# MAX96751_PINOUT.net
KiCad netlist of a schematic drawn in Altium Designer
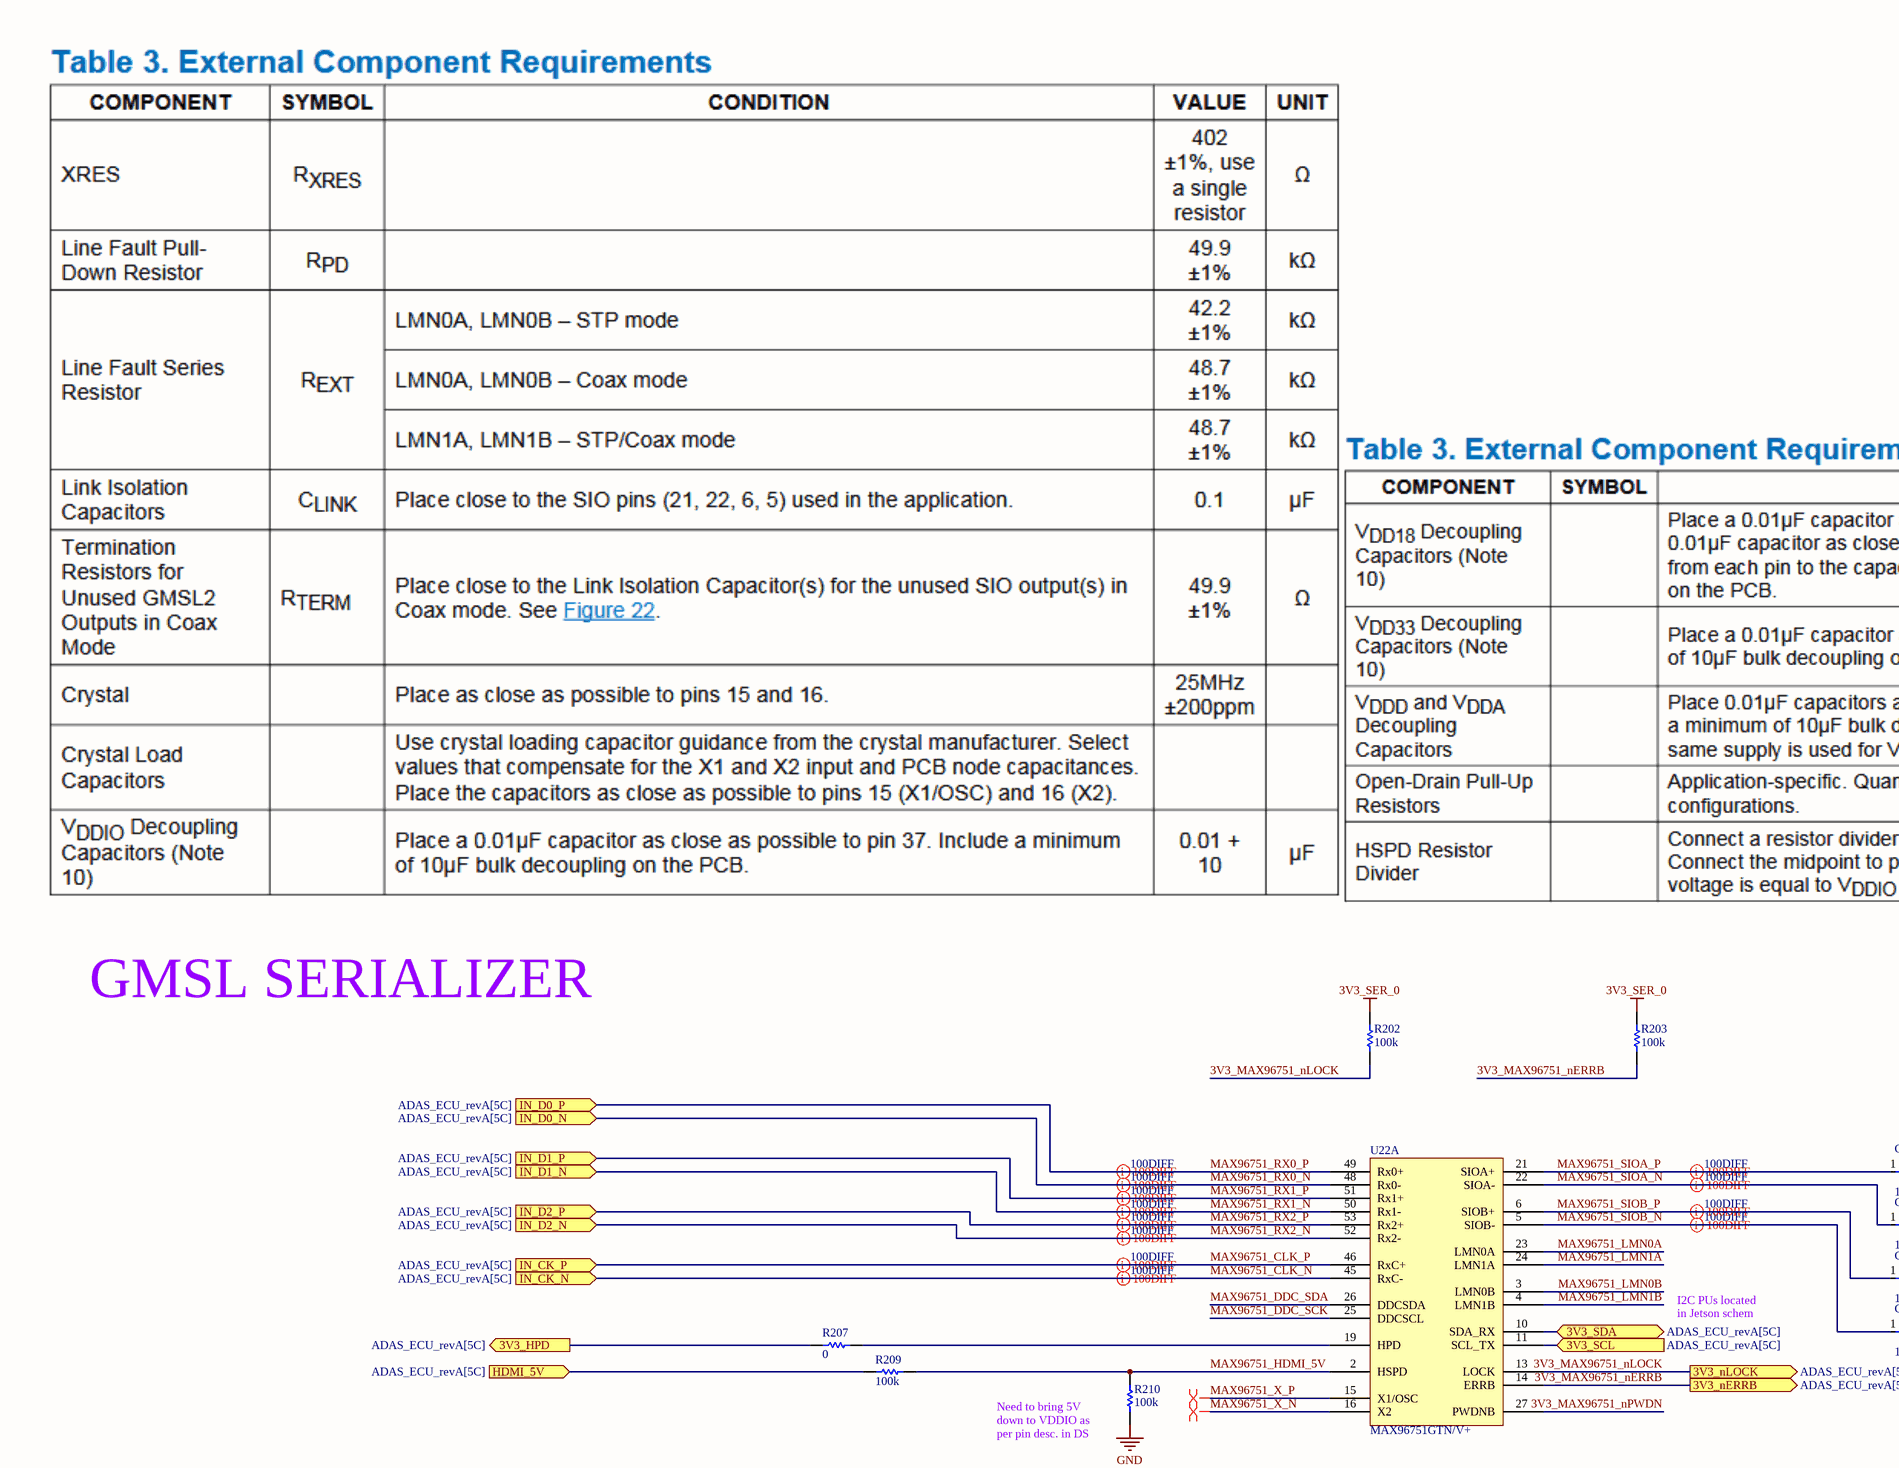
[diagram p0: MAX96751_PINOUT.SchDoc, top left]
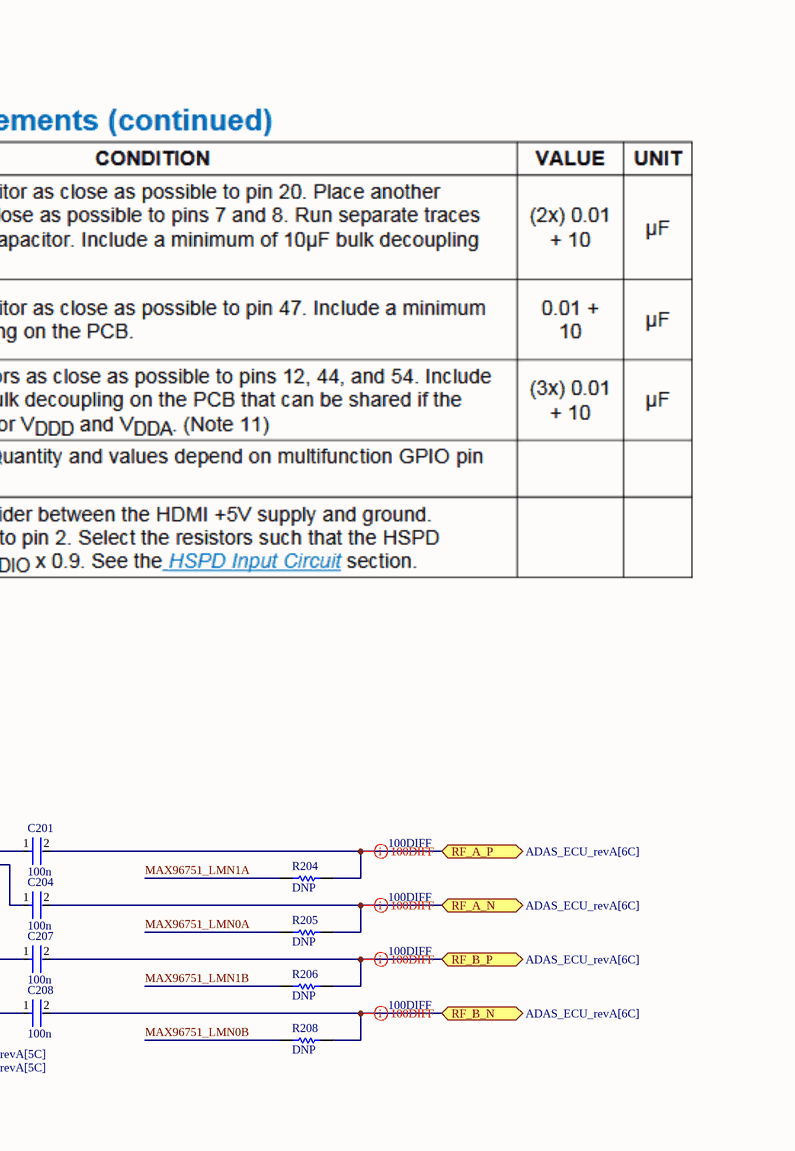
[diagram p1: MAX96751_PINOUT.SchDoc, top right]
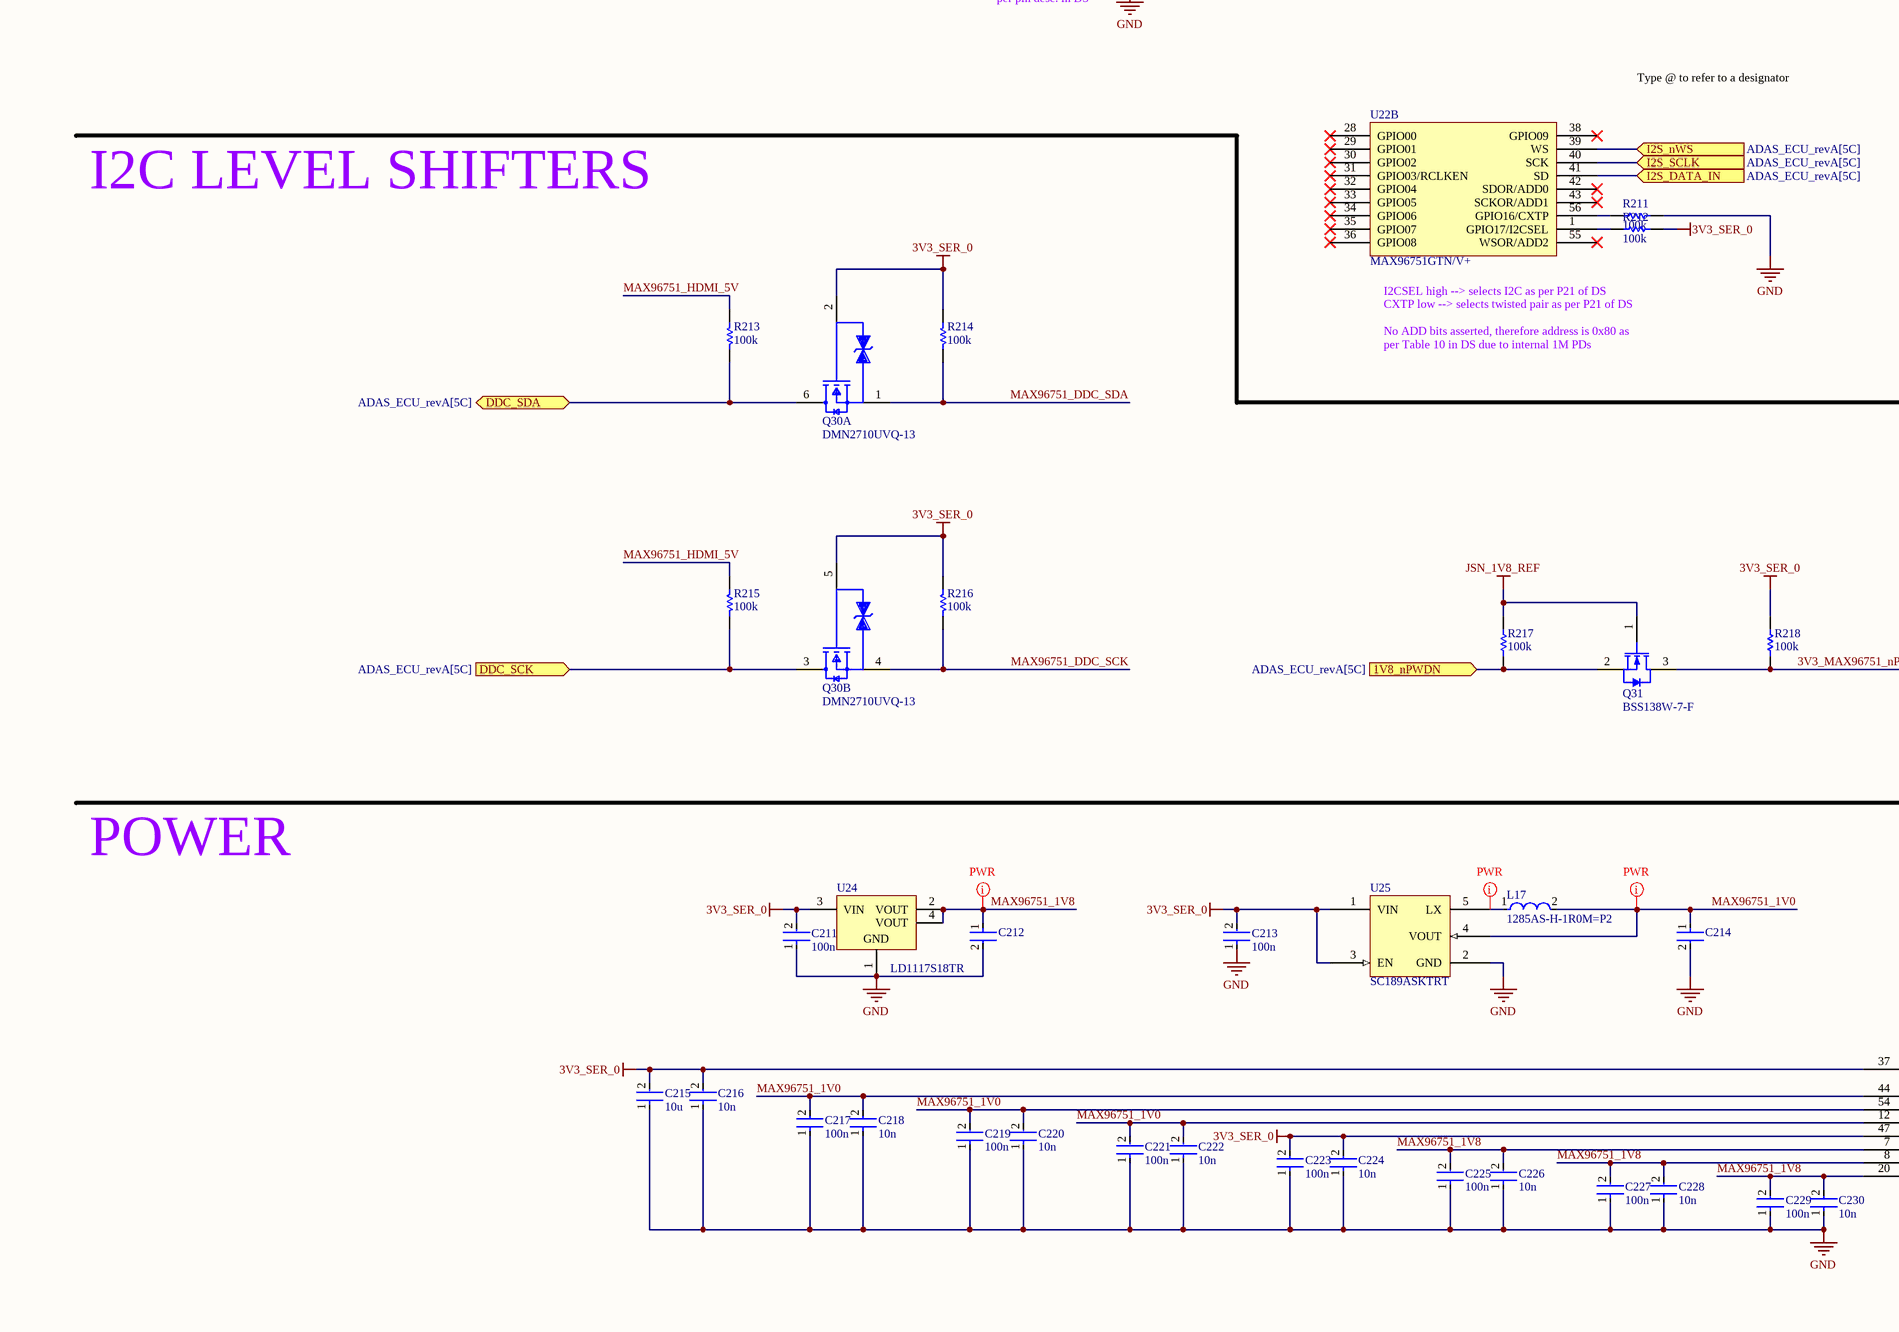
[diagram p2: MAX96751_PINOUT.SchDoc, bottom left]
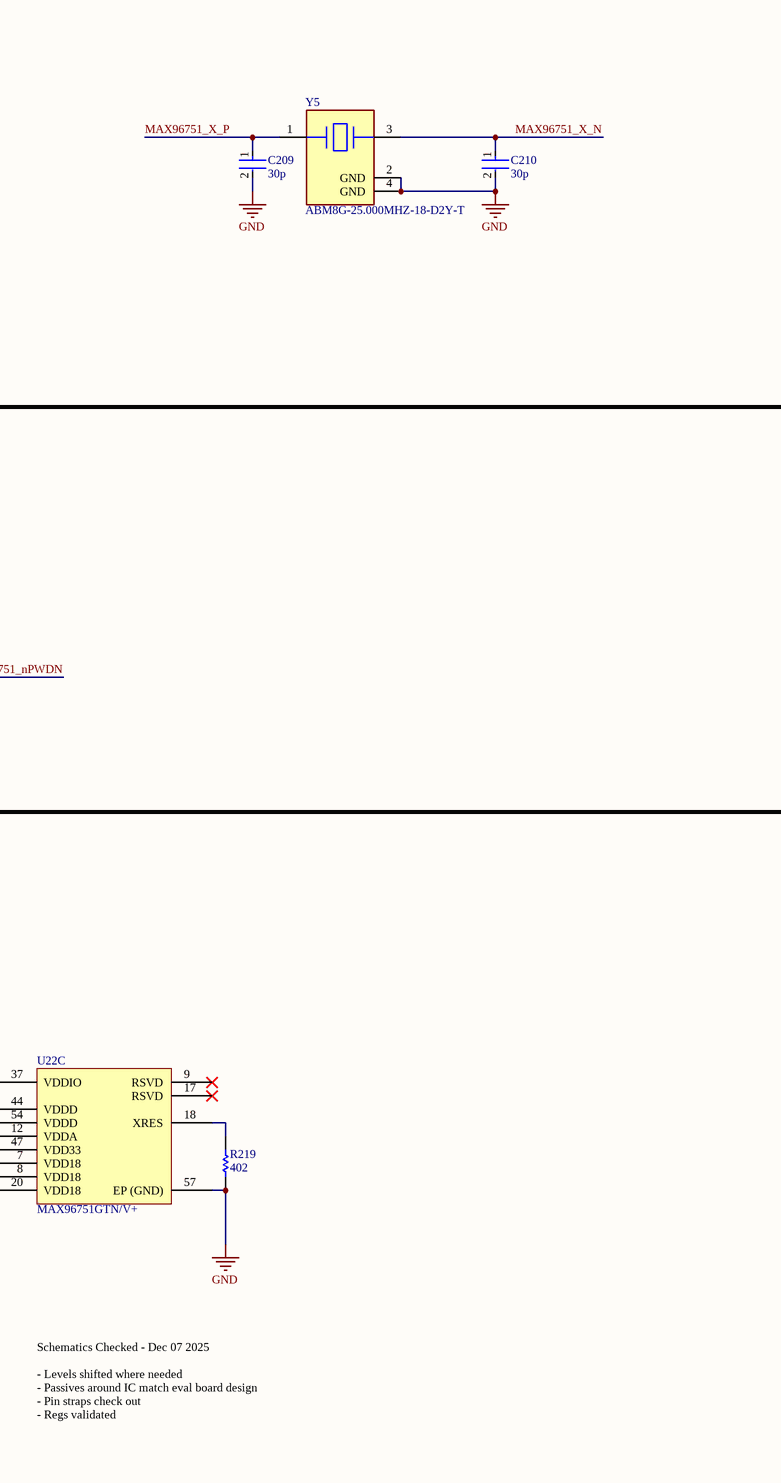
[diagram p3: MAX96751_PINOUT.SchDoc, bottom right]

(export (version "E")
  (design (tool "Eeschema 10.0.6"))
  (components
    (comp (ref "C201")
      (value "100n")
      (footprint "FP-0402-L_1_0_0_05-W_0_5-IPC_A")
      (description "LARGE PADS, 0402 CAP, CHANGE COMMENT TO MATCH REAL P/N")
      (libsource (lib "Space Concordia") (part "b4654b650e69147ec39a6b967a45e02"))
    )
    (comp (ref "C204")
      (value "100n")
      (footprint "FP-0402-L_1_0_0_05-W_0_5-IPC_A")
      (description "LARGE PADS, 0402 CAP, CHANGE COMMENT TO MATCH REAL P/N")
      (libsource (lib "Space Concordia") (part "b4654b650e69147ec39a6b967a45e02"))
    )
    (comp (ref "C207")
      (value "100n")
      (footprint "FP-0402-L_1_0_0_05-W_0_5-IPC_A")
      (description "LARGE PADS, 0402 CAP, CHANGE COMMENT TO MATCH REAL P/N")
      (libsource (lib "Space Concordia") (part "b4654b650e69147ec39a6b967a45e02"))
    )
    (comp (ref "C208")
      (value "100n")
      (footprint "FP-0402-L_1_0_0_05-W_0_5-IPC_A")
      (description "LARGE PADS, 0402 CAP, CHANGE COMMENT TO MATCH REAL P/N")
      (libsource (lib "Space Concordia") (part "b4654b650e69147ec39a6b967a45e02"))
    )
    (comp (ref "C209")
      (value "30p")
      (footprint "FP-0402-L_1_0_0_05-W_0_5-IPC_A")
      (description "LARGE PADS, 0402 CAP, CHANGE COMMENT TO MATCH REAL P/N")
      (libsource (lib "Space Concordia") (part "b4654b650e69147ec39a6b967a45e02"))
    )
    (comp (ref "C210")
      (value "30p")
      (footprint "FP-0402-L_1_0_0_05-W_0_5-IPC_A")
      (description "LARGE PADS, 0402 CAP, CHANGE COMMENT TO MATCH REAL P/N")
      (libsource (lib "Space Concordia") (part "b4654b650e69147ec39a6b967a45e02"))
    )
    (comp (ref "C211")
      (value "100n")
      (footprint "FP-0402-L_1_0_0_05-W_0_5-IPC_A")
      (description "LARGE PADS, 0402 CAP, CHANGE COMMENT TO MATCH REAL P/N")
      (libsource (lib "Space Concordia") (part "b4654b650e69147ec39a6b967a45e02"))
    )
    (comp (ref "C212")
      (value "GRM188R60J106ME47D")
      (footprint "FP-GRM188-0_1-e0_2_0_55-IPC_A")
      (description "Chip Multilayer Ceramic Capacitors for General Purpose, 0603, 10uF, X5R, 15%, 20%, 6.3V")
      (fields (field (name "VOLTAGE") "6.3V") (field (name "TOLERANCE") "20%"))
      (libsource (lib "Altium Content Vault") (part "02cd4be3c70576c341d710602a673aa"))
    )
    (comp (ref "C213")
      (value "100n")
      (footprint "FP-0402-L_1_0_0_05-W_0_5-IPC_A")
      (description "LARGE PADS, 0402 CAP, CHANGE COMMENT TO MATCH REAL P/N")
      (libsource (lib "Space Concordia") (part "b4654b650e69147ec39a6b967a45e02"))
    )
    (comp (ref "C214")
      (value "GRM21BR61E226ME44L")
      (footprint "FP-GRM21B-0_2-e0_2_0_7-IPC_B")
      (description "Chip Multilayer Ceramic Capacitors for General Purpose, 0805, 22uF, X5R, 15%, 20%, 25V")
      (fields (field (name "TOLERANCE") "20%") (field (name "VOLTAGE") "25V"))
      (libsource (lib "Altium Content Vault") (part "b4654b650e69147ec39a6b967a45e02"))
    )
    (comp (ref "C215")
      (value "10u")
      (footprint "FP-0402-L_1_0_0_05-W_0_5-IPC_A")
      (description "LARGE PADS, 0402 CAP, CHANGE COMMENT TO MATCH REAL P/N")
      (libsource (lib "Space Concordia") (part "b4654b650e69147ec39a6b967a45e02"))
    )
    (comp (ref "C216")
      (value "10n")
      (footprint "FP-0402-L_1_0_0_05-W_0_5-IPC_A")
      (description "LARGE PADS, 0402 CAP, CHANGE COMMENT TO MATCH REAL P/N")
      (libsource (lib "Space Concordia") (part "b4654b650e69147ec39a6b967a45e02"))
    )
    (comp (ref "C217")
      (value "100n")
      (footprint "FP-0402-L_1_0_0_05-W_0_5-IPC_A")
      (description "LARGE PADS, 0402 CAP, CHANGE COMMENT TO MATCH REAL P/N")
      (libsource (lib "Space Concordia") (part "b4654b650e69147ec39a6b967a45e02"))
    )
    (comp (ref "C218")
      (value "10n")
      (footprint "FP-0402-L_1_0_0_05-W_0_5-IPC_A")
      (description "LARGE PADS, 0402 CAP, CHANGE COMMENT TO MATCH REAL P/N")
      (libsource (lib "Space Concordia") (part "b4654b650e69147ec39a6b967a45e02"))
    )
    (comp (ref "C219")
      (value "100n")
      (footprint "FP-0402-L_1_0_0_05-W_0_5-IPC_A")
      (description "LARGE PADS, 0402 CAP, CHANGE COMMENT TO MATCH REAL P/N")
      (libsource (lib "Space Concordia") (part "b4654b650e69147ec39a6b967a45e02"))
    )
    (comp (ref "C220")
      (value "10n")
      (footprint "FP-0402-L_1_0_0_05-W_0_5-IPC_A")
      (description "LARGE PADS, 0402 CAP, CHANGE COMMENT TO MATCH REAL P/N")
      (libsource (lib "Space Concordia") (part "b4654b650e69147ec39a6b967a45e02"))
    )
    (comp (ref "C221")
      (value "100n")
      (footprint "FP-0402-L_1_0_0_05-W_0_5-IPC_A")
      (description "LARGE PADS, 0402 CAP, CHANGE COMMENT TO MATCH REAL P/N")
      (libsource (lib "Space Concordia") (part "b4654b650e69147ec39a6b967a45e02"))
    )
    (comp (ref "C222")
      (value "10n")
      (footprint "FP-0402-L_1_0_0_05-W_0_5-IPC_A")
      (description "LARGE PADS, 0402 CAP, CHANGE COMMENT TO MATCH REAL P/N")
      (libsource (lib "Space Concordia") (part "b4654b650e69147ec39a6b967a45e02"))
    )
    (comp (ref "C223")
      (value "100n")
      (footprint "FP-0402-L_1_0_0_05-W_0_5-IPC_A")
      (description "LARGE PADS, 0402 CAP, CHANGE COMMENT TO MATCH REAL P/N")
      (libsource (lib "Space Concordia") (part "b4654b650e69147ec39a6b967a45e02"))
    )
    (comp (ref "C224")
      (value "10n")
      (footprint "FP-0402-L_1_0_0_05-W_0_5-IPC_A")
      (description "LARGE PADS, 0402 CAP, CHANGE COMMENT TO MATCH REAL P/N")
      (libsource (lib "Space Concordia") (part "b4654b650e69147ec39a6b967a45e02"))
    )
    (comp (ref "C225")
      (value "100n")
      (footprint "FP-0402-L_1_0_0_05-W_0_5-IPC_A")
      (description "LARGE PADS, 0402 CAP, CHANGE COMMENT TO MATCH REAL P/N")
      (libsource (lib "Space Concordia") (part "b4654b650e69147ec39a6b967a45e02"))
    )
    (comp (ref "C226")
      (value "10n")
      (footprint "FP-0402-L_1_0_0_05-W_0_5-IPC_A")
      (description "LARGE PADS, 0402 CAP, CHANGE COMMENT TO MATCH REAL P/N")
      (libsource (lib "Space Concordia") (part "b4654b650e69147ec39a6b967a45e02"))
    )
    (comp (ref "C227")
      (value "100n")
      (footprint "FP-0402-L_1_0_0_05-W_0_5-IPC_A")
      (description "LARGE PADS, 0402 CAP, CHANGE COMMENT TO MATCH REAL P/N")
      (libsource (lib "Space Concordia") (part "b4654b650e69147ec39a6b967a45e02"))
    )
    (comp (ref "C228")
      (value "10n")
      (footprint "FP-0402-L_1_0_0_05-W_0_5-IPC_A")
      (description "LARGE PADS, 0402 CAP, CHANGE COMMENT TO MATCH REAL P/N")
      (libsource (lib "Space Concordia") (part "b4654b650e69147ec39a6b967a45e02"))
    )
    (comp (ref "C229")
      (value "100n")
      (footprint "FP-0402-L_1_0_0_05-W_0_5-IPC_A")
      (description "LARGE PADS, 0402 CAP, CHANGE COMMENT TO MATCH REAL P/N")
      (libsource (lib "Space Concordia") (part "b4654b650e69147ec39a6b967a45e02"))
    )
    (comp (ref "C230")
      (value "10n")
      (footprint "FP-0402-L_1_0_0_05-W_0_5-IPC_A")
      (description "LARGE PADS, 0402 CAP, CHANGE COMMENT TO MATCH REAL P/N")
      (libsource (lib "Space Concordia") (part "b4654b650e69147ec39a6b967a45e02"))
    )
    (comp (ref "L17")
      (value "1285AS-H-1R0M=P2")
      (footprint "FP-DFE201610C-MFG")
      (description "FIXED IND 1UH 2.2A 96 MOHM SMD")
      (fields (field (name "TOLERANCE") "20%"))
      (libsource (lib "Altium Content Vault") (part "725321dda6339637d4d059423bc1c3c"))
    )
    (comp (ref "Q30")
      (value "DMN2710UVQ-13")
      (footprint "SOTFL50P162X60-6N")
      (description "MOSFET Array, Dual N Channel, 20 V, 920 mA, 450 Milliohms, SOT-563, 6 Pins")
      (libsource (lib "Space Concordia") (part "DMN2710UVQ-13"))
    )
    (comp (ref "Q31")
      (value "BSS138W-7-F")
      (footprint "DIOD-SOT323-3_V")
      (fields (field (name "MANUFACTURER") "DiodesIncorporated"))
      (libsource (lib "Altium Content Vault") (part "NEMOS-GSD-3"))
    )
    (comp (ref "R202")
      (value "100k")
      (footprint "R0603B")
      (description "Resistor")
      (libsource (lib "Space Concordia") (part "Resistor"))
    )
    (comp (ref "R203")
      (value "100k")
      (footprint "R0603B")
      (description "Resistor")
      (libsource (lib "Space Concordia") (part "Resistor"))
    )
    (comp (ref "R204")
      (value "DNP")
      (footprint "R0603B")
      (description "Resistor")
      (libsource (lib "Space Concordia") (part "Resistor"))
    )
    (comp (ref "R205")
      (value "DNP")
      (footprint "R0603B")
      (description "Resistor")
      (libsource (lib "Space Concordia") (part "Resistor"))
    )
    (comp (ref "R206")
      (value "DNP")
      (footprint "R0603B")
      (description "Resistor")
      (libsource (lib "Space Concordia") (part "Resistor"))
    )
    (comp (ref "R207")
      (value "0")
      (footprint "R0603B")
      (description "Resistor")
      (libsource (lib "Space Concordia") (part "Resistor"))
    )
    (comp (ref "R208")
      (value "DNP")
      (footprint "R0603B")
      (description "Resistor")
      (libsource (lib "Space Concordia") (part "Resistor"))
    )
    (comp (ref "R209")
      (value "100k")
      (footprint "R0603B")
      (description "Resistor")
      (libsource (lib "Space Concordia") (part "Resistor"))
    )
    (comp (ref "R210")
      (value "100k")
      (footprint "R0603B")
      (description "Resistor")
      (libsource (lib "Space Concordia") (part "Resistor"))
    )
    (comp (ref "R211")
      (value "100k")
      (footprint "R0603B")
      (description "Resistor")
      (libsource (lib "Space Concordia") (part "Resistor"))
    )
    (comp (ref "R212")
      (value "100k")
      (footprint "R0603B")
      (description "Resistor")
      (libsource (lib "Space Concordia") (part "Resistor"))
    )
    (comp (ref "R213")
      (value "100k")
      (footprint "R0603B")
      (description "Resistor")
      (libsource (lib "Space Concordia") (part "Resistor"))
    )
    (comp (ref "R214")
      (value "100k")
      (footprint "R0603B")
      (description "Resistor")
      (libsource (lib "Space Concordia") (part "Resistor"))
    )
    (comp (ref "R215")
      (value "100k")
      (footprint "R0603B")
      (description "Resistor")
      (libsource (lib "Space Concordia") (part "Resistor"))
    )
    (comp (ref "R216")
      (value "100k")
      (footprint "R0603B")
      (description "Resistor")
      (libsource (lib "Space Concordia") (part "Resistor"))
    )
    (comp (ref "R217")
      (value "100k")
      (footprint "R0603B")
      (description "Resistor")
      (libsource (lib "Space Concordia") (part "Resistor"))
    )
    (comp (ref "R218")
      (value "100k")
      (footprint "R0603B")
      (description "Resistor")
      (libsource (lib "Space Concordia") (part "Resistor"))
    )
    (comp (ref "R219")
      (value "402")
      (footprint "R0603B")
      (description "Resistor")
      (libsource (lib "Space Concordia") (part "Resistor"))
    )
    (comp (ref "U22")
      (value "MAX96751GTN/V+")
      (footprint "QFN50P800X800X80_HS-57N")
      (description "GMSL2 Serializer with HDMI 2.0 Input")
      (libsource (lib "Space Concordia") (part "MAX96751GTN_V+"))
    )
    (comp (ref "U24")
      (value "LD1117S18TR")
      (footprint "SOT-223_M")
      (description "Fixed Low Drop Positive Voltage Regulator, 1.8V, 4-Pin SOT-223, Tape and Reel")
      (libsource (lib "Altium Content Vault") (part "PM-REG-LD1117-SOT4"))
    )
    (comp (ref "U25")
      (value "SC189ASKTRT")
      (footprint "SOT95P275X145-5N")
      (description "Switching Regulator, Voltage-mode, 1.5A, 3000kHz Switching Freq-Max, PDSO5")
      (libsource (lib "Space Concordia") (part "SC189ASKTRT"))
    )
    (comp (ref "Y5")
      (value "ABM8G-25.000MHZ-18-D2Y-T")
      (footprint "FP-ABM8G-MFG")
      (description "Crystal 25MHz ±20ppm (Tol) ±30ppm (Stability) 18pF FUND 60Ω 4-Pin SMD T/R")
      (fields (field (name "TOLERANCE") "20ppm"))
      (libsource (lib "Altium Content Vault") (part "48e526d86b7f2615d98721063c72f49"))
    )
  )
  (nets
    (net (code "1") (name "/1V8_nPWDN") (class "Default")
      (node (ref "Q31") (pin "2") (pinfunction "S_2") (pintype "passive"))
      (node (ref "R217") (pin "1") (pinfunction "1_1") (pintype "passive"))
    )
    (net (code "2") (name "/3V3_HPD") (class "Default")
      (node (ref "R207") (pin "2") (pinfunction "2_2") (pintype "passive"))
    )
    (net (code "3") (name "/3V3_MAX96751_nERRB") (class "Default")
      (node (ref "R203") (pin "1") (pinfunction "1_1") (pintype "passive"))
      (node (ref "U22") (pin "14") (pinfunction "ERRB_14") (pintype "passive"))
    )
    (net (code "4") (name "/3V3_MAX96751_nLOCK") (class "Default")
      (node (ref "R202") (pin "1") (pinfunction "1_1") (pintype "passive"))
      (node (ref "U22") (pin "13") (pinfunction "LOCK_13") (pintype "passive"))
    )
    (net (code "5") (name "/3V3_MAX96751_nPWDN") (class "Default")
      (node (ref "Q31") (pin "3") (pinfunction "D_3") (pintype "passive"))
      (node (ref "R218") (pin "1") (pinfunction "1_1") (pintype "passive"))
      (node (ref "U22") (pin "27") (pinfunction "PWDNB_27") (pintype "passive"))
    )
    (net (code "6") (name "/3V3_SCL") (class "Default")
      (node (ref "U22") (pin "11") (pinfunction "SCL_TX_11") (pintype "passive"))
    )
    (net (code "7") (name "/3V3_SDA") (class "Default")
      (node (ref "U22") (pin "10") (pinfunction "SDA_RX_10") (pintype "passive"))
    )
    (net (code "8") (name "/DDC_SCK") (class "Default")
      (node (ref "Q30") (pin "3") (pinfunction "Drain2_3") (pintype "passive"))
      (node (ref "R215") (pin "1") (pinfunction "1_1") (pintype "passive"))
    )
    (net (code "9") (name "/DDC_SDA") (class "Default")
      (node (ref "Q30") (pin "6") (pinfunction "Drain1_6") (pintype "passive"))
      (node (ref "R213") (pin "1") (pinfunction "1_1") (pintype "passive"))
    )
    (net (code "10") (name "/HDMI_5V") (class "Default")
      (node (ref "R209") (pin "2") (pinfunction "2_2") (pintype "passive"))
    )
    (net (code "11") (name "/I2S_DATA_IN") (class "Default")
      (node (ref "U22") (pin "41") (pinfunction "SD_41") (pintype "passive"))
    )
    (net (code "12") (name "/I2S_SCLK") (class "Default")
      (node (ref "U22") (pin "40") (pinfunction "SCK_40") (pintype "passive"))
    )
    (net (code "13") (name "/I2S_nWS") (class "Default")
      (node (ref "U22") (pin "39") (pinfunction "WS_39") (pintype "passive"))
    )
    (net (code "14") (name "/MAX96751_1V0") (class "Default")
      (node (ref "C214") (pin "1") (pinfunction "1_1") (pintype "passive"))
      (node (ref "C217") (pin "2") (pinfunction "2_2") (pintype "passive"))
      (node (ref "C218") (pin "2") (pinfunction "2_2") (pintype "passive"))
      (node (ref "C219") (pin "2") (pinfunction "2_2") (pintype "passive"))
      (node (ref "C220") (pin "2") (pinfunction "2_2") (pintype "passive"))
      (node (ref "C221") (pin "2") (pinfunction "2_2") (pintype "passive"))
      (node (ref "C222") (pin "2") (pinfunction "2_2") (pintype "passive"))
      (node (ref "L17") (pin "2") (pinfunction "2_2") (pintype "passive"))
      (node (ref "U22") (pin "12") (pinfunction "VDDA_12") (pintype "passive"))
      (node (ref "U22") (pin "44") (pinfunction "VDDD_44") (pintype "passive"))
      (node (ref "U22") (pin "54") (pinfunction "VDDD_54") (pintype "passive"))
      (node (ref "U25") (pin "4") (pinfunction "VOUT_4") (pintype "input"))
    )
    (net (code "15") (name "/MAX96751_1V8") (class "Default")
      (node (ref "C212") (pin "1") (pinfunction "1_1") (pintype "passive"))
      (node (ref "C225") (pin "2") (pinfunction "2_2") (pintype "passive"))
      (node (ref "C226") (pin "2") (pinfunction "2_2") (pintype "passive"))
      (node (ref "C227") (pin "2") (pinfunction "2_2") (pintype "passive"))
      (node (ref "C228") (pin "2") (pinfunction "2_2") (pintype "passive"))
      (node (ref "C229") (pin "2") (pinfunction "2_2") (pintype "passive"))
      (node (ref "C230") (pin "2") (pinfunction "2_2") (pintype "passive"))
      (node (ref "U22") (pin "20") (pinfunction "VDD18_20") (pintype "passive"))
      (node (ref "U22") (pin "7") (pinfunction "VDD18_7") (pintype "passive"))
      (node (ref "U22") (pin "8") (pinfunction "VDD18_8") (pintype "passive"))
      (node (ref "U24") (pin "2") (pinfunction "VOUT_2") (pintype "power_in"))
      (node (ref "U24") (pin "4") (pinfunction "VOUT_4") (pintype "power_in"))
    )
    (net (code "16") (name "/MAX96751_CLK_N") (class "Default")
      (node (ref "U22") (pin "45") (pinfunction "RxC-_45") (pintype "passive"))
    )
    (net (code "17") (name "/MAX96751_CLK_P") (class "Default")
      (node (ref "U22") (pin "46") (pinfunction "RxC+_46") (pintype "passive"))
    )
    (net (code "18") (name "/MAX96751_DDC_SCK") (class "Default")
      (node (ref "Q30") (pin "4") (pinfunction "Source2_4") (pintype "passive"))
      (node (ref "R216") (pin "1") (pinfunction "1_1") (pintype "passive"))
      (node (ref "U22") (pin "25") (pinfunction "DDCSCL_25") (pintype "passive"))
    )
    (net (code "19") (name "/MAX96751_DDC_SDA") (class "Default")
      (node (ref "Q30") (pin "1") (pinfunction "Source1_1") (pintype "passive"))
      (node (ref "R214") (pin "1") (pinfunction "1_1") (pintype "passive"))
      (node (ref "U22") (pin "26") (pinfunction "DDCSDA_26") (pintype "passive"))
    )
    (net (code "20") (name "/MAX96751_HDMI_5V") (class "Default")
      (node (ref "R209") (pin "1") (pinfunction "1_1") (pintype "passive"))
      (node (ref "R210") (pin "1") (pinfunction "1_1") (pintype "passive"))
      (node (ref "R213") (pin "2") (pinfunction "2_2") (pintype "passive"))
      (node (ref "R215") (pin "2") (pinfunction "2_2") (pintype "passive"))
      (node (ref "U22") (pin "2") (pinfunction "HSPD_2") (pintype "passive"))
    )
    (net (code "21") (name "/MAX96751_LMN0A") (class "Default")
      (node (ref "R205") (pin "2") (pinfunction "2_2") (pintype "passive"))
      (node (ref "U22") (pin "23") (pinfunction "LMN0A_23") (pintype "passive"))
    )
    (net (code "22") (name "/MAX96751_LMN0B") (class "Default")
      (node (ref "R208") (pin "2") (pinfunction "2_2") (pintype "passive"))
      (node (ref "U22") (pin "3") (pinfunction "LMN0B_3") (pintype "passive"))
    )
    (net (code "23") (name "/MAX96751_LMN1A") (class "Default")
      (node (ref "R204") (pin "2") (pinfunction "2_2") (pintype "passive"))
      (node (ref "U22") (pin "24") (pinfunction "LMN1A_24") (pintype "passive"))
    )
    (net (code "24") (name "/MAX96751_LMN1B") (class "Default")
      (node (ref "R206") (pin "2") (pinfunction "2_2") (pintype "passive"))
      (node (ref "U22") (pin "4") (pinfunction "LMN1B_4") (pintype "passive"))
    )
    (net (code "25") (name "/MAX96751_RX0_N") (class "Default")
      (node (ref "U22") (pin "48") (pinfunction "Rx0-_48") (pintype "passive"))
    )
    (net (code "26") (name "/MAX96751_RX0_P") (class "Default")
      (node (ref "U22") (pin "49") (pinfunction "Rx0+_49") (pintype "passive"))
    )
    (net (code "27") (name "/MAX96751_RX1_N") (class "Default")
      (node (ref "U22") (pin "50") (pinfunction "Rx1-_50") (pintype "passive"))
    )
    (net (code "28") (name "/MAX96751_RX1_P") (class "Default")
      (node (ref "U22") (pin "51") (pinfunction "Rx1+_51") (pintype "passive"))
    )
    (net (code "29") (name "/MAX96751_RX2_N") (class "Default")
      (node (ref "U22") (pin "52") (pinfunction "Rx2-_52") (pintype "passive"))
    )
    (net (code "30") (name "/MAX96751_RX2_P") (class "Default")
      (node (ref "U22") (pin "53") (pinfunction "Rx2+_53") (pintype "passive"))
    )
    (net (code "31") (name "/MAX96751_SIOA_N") (class "Default")
      (node (ref "C204") (pin "1") (pinfunction "1_1") (pintype "passive"))
      (node (ref "U22") (pin "22") (pinfunction "SIOA-_22") (pintype "passive"))
    )
    (net (code "32") (name "/MAX96751_SIOA_P") (class "Default")
      (node (ref "C201") (pin "1") (pinfunction "1_1") (pintype "passive"))
      (node (ref "U22") (pin "21") (pinfunction "SIOA+_21") (pintype "passive"))
    )
    (net (code "33") (name "/MAX96751_SIOB_N") (class "Default")
      (node (ref "C208") (pin "1") (pinfunction "1_1") (pintype "passive"))
      (node (ref "U22") (pin "5") (pinfunction "SIOB-_5") (pintype "passive"))
    )
    (net (code "34") (name "/MAX96751_SIOB_P") (class "Default")
      (node (ref "C207") (pin "1") (pinfunction "1_1") (pintype "passive"))
      (node (ref "U22") (pin "6") (pinfunction "SIOB+_6") (pintype "passive"))
    )
    (net (code "35") (name "/MAX96751_X_N") (class "Default")
      (node (ref "C210") (pin "1") (pinfunction "1_1") (pintype "passive"))
      (node (ref "U22") (pin "16") (pinfunction "X2_16") (pintype "passive"))
      (node (ref "Y5") (pin "3") (pinfunction "3_3") (pintype "passive"))
    )
    (net (code "36") (name "/MAX96751_X_P") (class "Default")
      (node (ref "C209") (pin "1") (pinfunction "1_1") (pintype "passive"))
      (node (ref "U22") (pin "15") (pinfunction "X1/OSC_15") (pintype "passive"))
      (node (ref "Y5") (pin "1") (pinfunction "1_1") (pintype "passive"))
    )
    (net (code "37") (name "/RF_A_N") (class "Default")
      (node (ref "C204") (pin "2") (pinfunction "2_2") (pintype "passive"))
      (node (ref "R205") (pin "1") (pinfunction "1_1") (pintype "passive"))
    )
    (net (code "38") (name "/RF_A_P") (class "Default")
      (node (ref "C201") (pin "2") (pinfunction "2_2") (pintype "passive"))
      (node (ref "R204") (pin "1") (pinfunction "1_1") (pintype "passive"))
    )
    (net (code "39") (name "/RF_B_N") (class "Default")
      (node (ref "C208") (pin "2") (pinfunction "2_2") (pintype "passive"))
      (node (ref "R208") (pin "1") (pinfunction "1_1") (pintype "passive"))
    )
    (net (code "40") (name "/RF_B_P") (class "Default")
      (node (ref "C207") (pin "2") (pinfunction "2_2") (pintype "passive"))
      (node (ref "R206") (pin "1") (pinfunction "1_1") (pintype "passive"))
    )
    (net (code "41") (name "3V3_SER_0") (class "Default")
      (node (ref "C211") (pin "2") (pinfunction "2_2") (pintype "passive"))
      (node (ref "C213") (pin "2") (pinfunction "2_2") (pintype "passive"))
      (node (ref "C215") (pin "2") (pinfunction "2_2") (pintype "passive"))
      (node (ref "C216") (pin "2") (pinfunction "2_2") (pintype "passive"))
      (node (ref "C223") (pin "2") (pinfunction "2_2") (pintype "passive"))
      (node (ref "C224") (pin "2") (pinfunction "2_2") (pintype "passive"))
      (node (ref "Q30") (pin "2") (pinfunction "Gate1_2") (pintype "passive"))
      (node (ref "Q30") (pin "5") (pinfunction "Gate2_5") (pintype "passive"))
      (node (ref "R202") (pin "2") (pinfunction "2_2") (pintype "passive"))
      (node (ref "R203") (pin "2") (pinfunction "2_2") (pintype "passive"))
      (node (ref "R212") (pin "2") (pinfunction "2_2") (pintype "passive"))
      (node (ref "R214") (pin "2") (pinfunction "2_2") (pintype "passive"))
      (node (ref "R216") (pin "2") (pinfunction "2_2") (pintype "passive"))
      (node (ref "R218") (pin "2") (pinfunction "2_2") (pintype "passive"))
      (node (ref "U22") (pin "37") (pinfunction "VDDIO_37") (pintype "passive"))
      (node (ref "U22") (pin "47") (pinfunction "VDD33_47") (pintype "passive"))
      (node (ref "U24") (pin "3") (pinfunction "VIN_3") (pintype "power_in"))
      (node (ref "U25") (pin "1") (pinfunction "VIN_1") (pintype "power_in"))
      (node (ref "U25") (pin "3") (pinfunction "EN_3") (pintype "input"))
    )
    (net (code "42") (name "GND") (class "Default")
      (node (ref "C209") (pin "2") (pinfunction "2_2") (pintype "passive"))
      (node (ref "C210") (pin "2") (pinfunction "2_2") (pintype "passive"))
      (node (ref "C211") (pin "1") (pinfunction "1_1") (pintype "passive"))
      (node (ref "C212") (pin "2") (pinfunction "2_2") (pintype "passive"))
      (node (ref "C213") (pin "1") (pinfunction "1_1") (pintype "passive"))
      (node (ref "C214") (pin "2") (pinfunction "2_2") (pintype "passive"))
      (node (ref "C215") (pin "1") (pinfunction "1_1") (pintype "passive"))
      (node (ref "C216") (pin "1") (pinfunction "1_1") (pintype "passive"))
      (node (ref "C217") (pin "1") (pinfunction "1_1") (pintype "passive"))
      (node (ref "C218") (pin "1") (pinfunction "1_1") (pintype "passive"))
      (node (ref "C219") (pin "1") (pinfunction "1_1") (pintype "passive"))
      (node (ref "C220") (pin "1") (pinfunction "1_1") (pintype "passive"))
      (node (ref "C221") (pin "1") (pinfunction "1_1") (pintype "passive"))
      (node (ref "C222") (pin "1") (pinfunction "1_1") (pintype "passive"))
      (node (ref "C223") (pin "1") (pinfunction "1_1") (pintype "passive"))
      (node (ref "C224") (pin "1") (pinfunction "1_1") (pintype "passive"))
      (node (ref "C225") (pin "1") (pinfunction "1_1") (pintype "passive"))
      (node (ref "C226") (pin "1") (pinfunction "1_1") (pintype "passive"))
      (node (ref "C227") (pin "1") (pinfunction "1_1") (pintype "passive"))
      (node (ref "C228") (pin "1") (pinfunction "1_1") (pintype "passive"))
      (node (ref "C229") (pin "1") (pinfunction "1_1") (pintype "passive"))
      (node (ref "C230") (pin "1") (pinfunction "1_1") (pintype "passive"))
      (node (ref "R210") (pin "2") (pinfunction "2_2") (pintype "passive"))
      (node (ref "R211") (pin "2") (pinfunction "2_2") (pintype "passive"))
      (node (ref "R219") (pin "2") (pinfunction "2_2") (pintype "passive"))
      (node (ref "U22") (pin "57") (pinfunction "EP_(GND)_57") (pintype "passive"))
      (node (ref "U24") (pin "1") (pinfunction "GND_1") (pintype "power_in"))
      (node (ref "U25") (pin "2") (pinfunction "GND_2") (pintype "power_in"))
      (node (ref "Y5") (pin "2") (pinfunction "GND_2") (pintype "power_in"))
      (node (ref "Y5") (pin "4") (pinfunction "GND_4") (pintype "power_in"))
    )
    (net (code "43") (name "JSN_1V8_REF") (class "Default")
      (node (ref "Q31") (pin "1") (pinfunction "G_1") (pintype "passive"))
      (node (ref "R217") (pin "2") (pinfunction "2_2") (pintype "passive"))
    )
    (net (code "44") (name "Net-(U22A-HPD)") (class "Default")
      (node (ref "R207") (pin "1") (pinfunction "1_1") (pintype "passive"))
      (node (ref "U22") (pin "19") (pinfunction "HPD_19") (pintype "passive"))
    )
    (net (code "45") (name "Net-(U22B-GPIO16{slash}CXTP)") (class "Default")
      (node (ref "R211") (pin "1") (pinfunction "1_1") (pintype "passive"))
      (node (ref "U22") (pin "56") (pinfunction "GPIO16/CXTP_56") (pintype "passive"))
    )
    (net (code "46") (name "Net-(U22B-GPIO17{slash}I2CSEL)") (class "Default")
      (node (ref "R212") (pin "1") (pinfunction "1_1") (pintype "passive"))
      (node (ref "U22") (pin "1") (pinfunction "GPIO17/I2CSEL_1") (pintype "passive"))
    )
    (net (code "47") (name "Net-(U22C-XRES)") (class "Default")
      (node (ref "R219") (pin "1") (pinfunction "1_1") (pintype "passive"))
      (node (ref "U22") (pin "18") (pinfunction "XRES_18") (pintype "passive"))
    )
    (net (code "48") (name "Net-(U25-LX)") (class "Default")
      (node (ref "L17") (pin "1") (pinfunction "1_1") (pintype "passive"))
      (node (ref "U25") (pin "5") (pinfunction "LX_5") (pintype "power_in"))
    )
    (net (code "49") (name "unconnected-(U22B-GPIO00-Pad28)") (class "Default")
      (node (ref "U22") (pin "28") (pinfunction "GPIO00_28") (pintype "passive+no_connect"))
    )
    (net (code "50") (name "unconnected-(U22B-GPIO01-Pad29)") (class "Default")
      (node (ref "U22") (pin "29") (pinfunction "GPIO01_29") (pintype "passive+no_connect"))
    )
    (net (code "51") (name "unconnected-(U22B-GPIO02-Pad30)") (class "Default")
      (node (ref "U22") (pin "30") (pinfunction "GPIO02_30") (pintype "passive+no_connect"))
    )
    (net (code "52") (name "unconnected-(U22B-GPIO03{slash}RCLKEN-Pad31)") (class "Default")
      (node (ref "U22") (pin "31") (pinfunction "GPIO03/RCLKEN_31") (pintype "passive+no_connect"))
    )
    (net (code "53") (name "unconnected-(U22B-GPIO04-Pad32)") (class "Default")
      (node (ref "U22") (pin "32") (pinfunction "GPIO04_32") (pintype "passive+no_connect"))
    )
    (net (code "54") (name "unconnected-(U22B-GPIO05-Pad33)") (class "Default")
      (node (ref "U22") (pin "33") (pinfunction "GPIO05_33") (pintype "passive+no_connect"))
    )
    (net (code "55") (name "unconnected-(U22B-GPIO06-Pad34)") (class "Default")
      (node (ref "U22") (pin "34") (pinfunction "GPIO06_34") (pintype "passive+no_connect"))
    )
    (net (code "56") (name "unconnected-(U22B-GPIO07-Pad35)") (class "Default")
      (node (ref "U22") (pin "35") (pinfunction "GPIO07_35") (pintype "passive+no_connect"))
    )
    (net (code "57") (name "unconnected-(U22B-GPIO08-Pad36)") (class "Default")
      (node (ref "U22") (pin "36") (pinfunction "GPIO08_36") (pintype "passive+no_connect"))
    )
    (net (code "58") (name "unconnected-(U22B-GPIO09-Pad38)") (class "Default")
      (node (ref "U22") (pin "38") (pinfunction "GPIO09_38") (pintype "passive+no_connect"))
    )
    (net (code "59") (name "unconnected-(U22B-SCKOR{slash}ADD1-Pad43)") (class "Default")
      (node (ref "U22") (pin "43") (pinfunction "SCKOR/ADD1_43") (pintype "passive+no_connect"))
    )
    (net (code "60") (name "unconnected-(U22B-SDOR{slash}ADD0-Pad42)") (class "Default")
      (node (ref "U22") (pin "42") (pinfunction "SDOR/ADD0_42") (pintype "passive+no_connect"))
    )
    (net (code "61") (name "unconnected-(U22B-WSOR{slash}ADD2-Pad55)") (class "Default")
      (node (ref "U22") (pin "55") (pinfunction "WSOR/ADD2_55") (pintype "passive+no_connect"))
    )
    (net (code "62") (name "unconnected-(U22C-RSVD-Pad9)") (class "Default")
      (node (ref "U22") (pin "9") (pinfunction "RSVD_9") (pintype "passive+no_connect"))
    )
    (net (code "63") (name "unconnected-(U22C-RSVD-Pad17)") (class "Default")
      (node (ref "U22") (pin "17") (pinfunction "RSVD_17") (pintype "passive+no_connect"))
    )
  )
)
